# Schematic.net
KiCad netlist of a schematic drawn in EasyEDA Pro
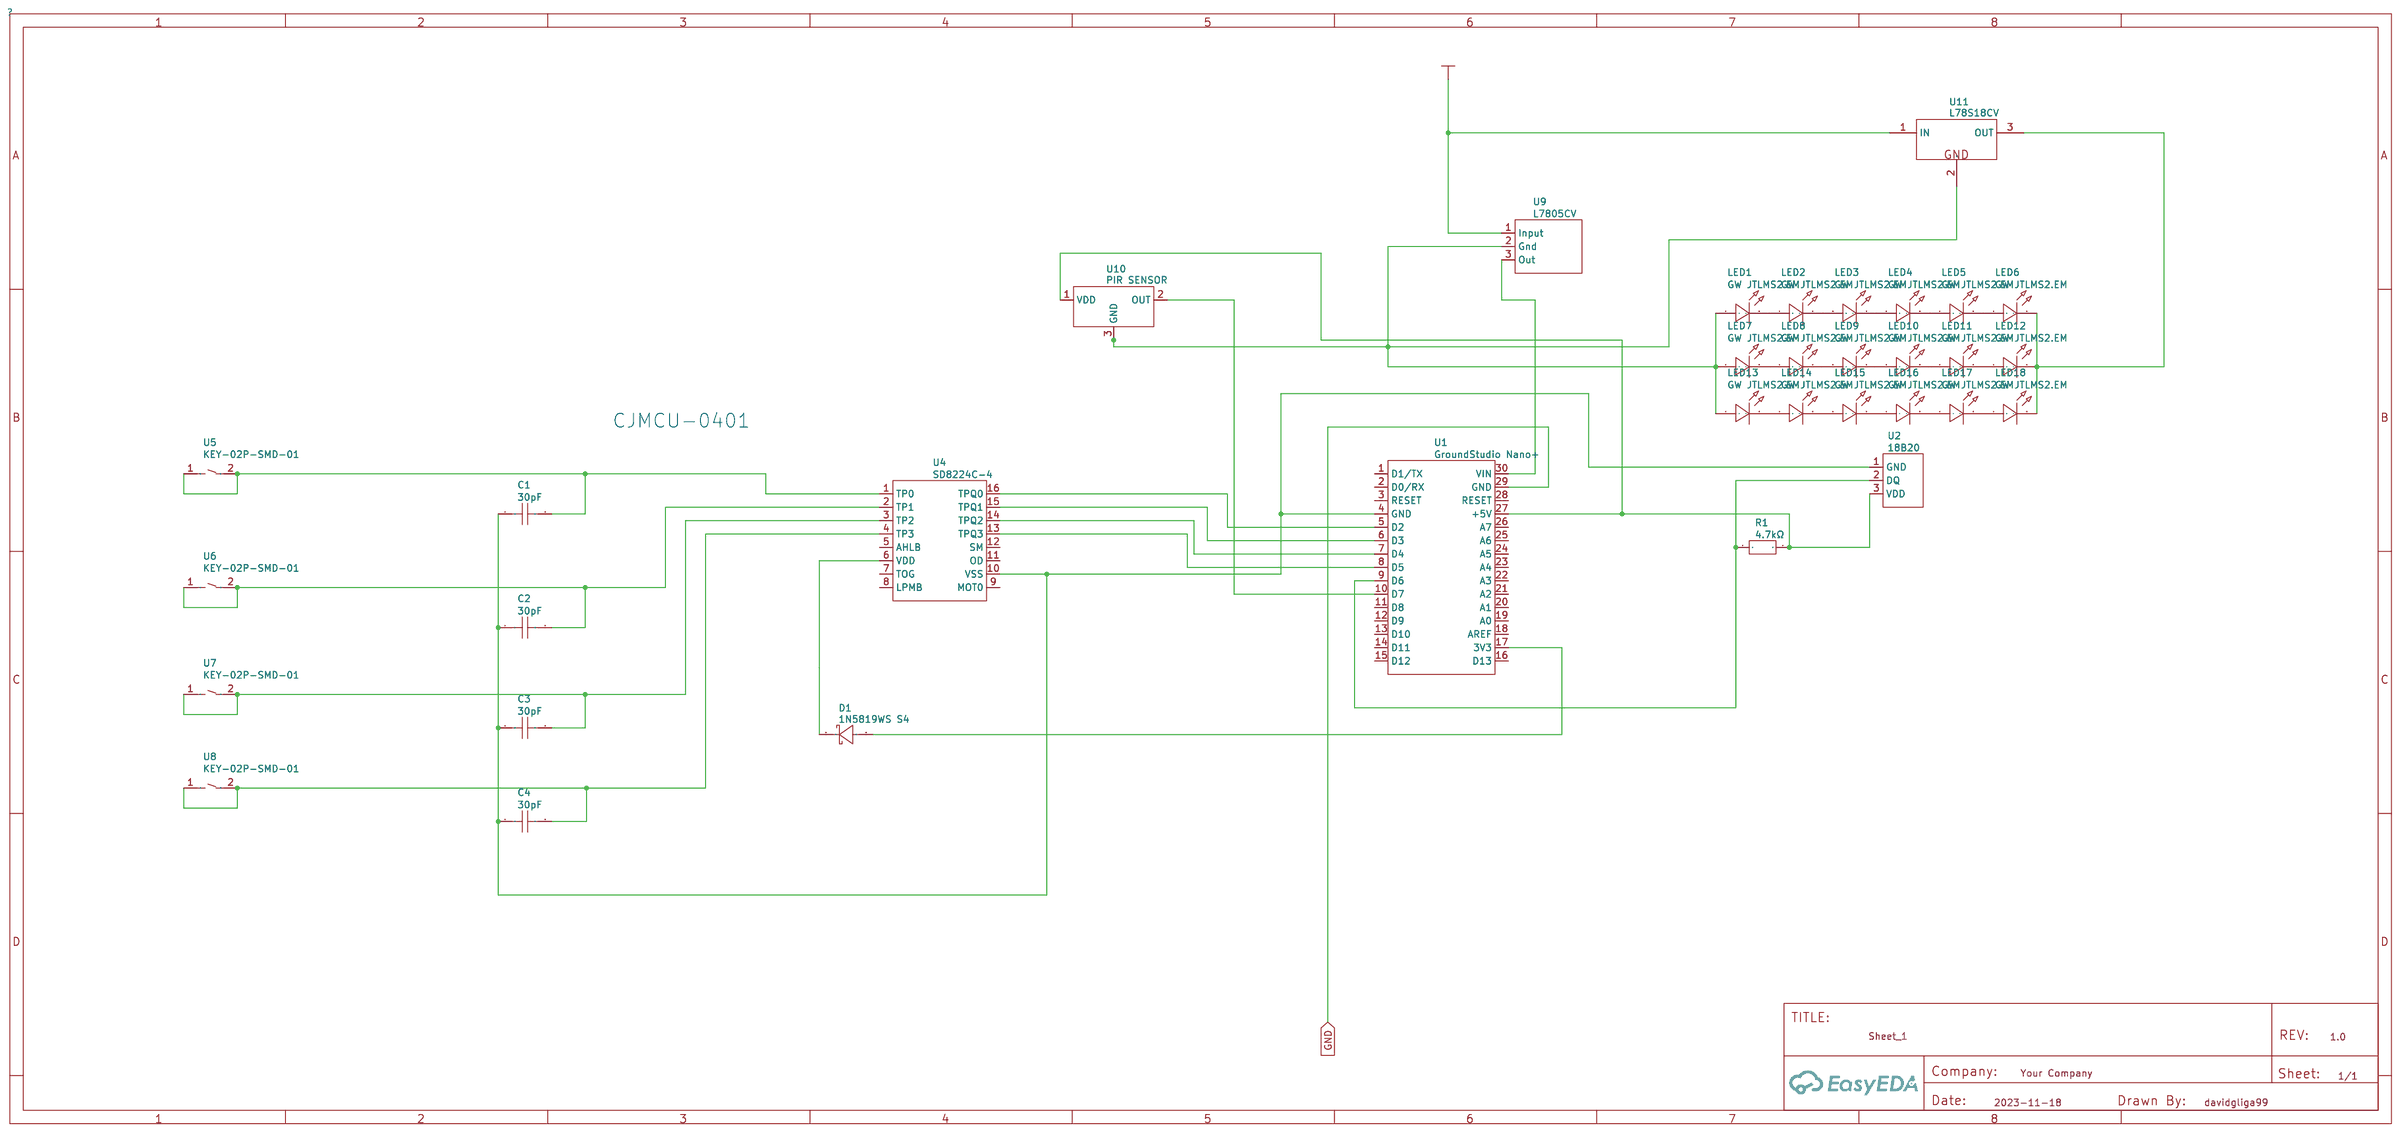
[diagram p0: schematic sheet]

(export (version "E")
  (design (tool "Eeschema 10.0.6"))
  (components
    (comp (ref "C1")
      (value "30pF")
      (footprint "easyedapro:C0402")
      (fields
        (field (name "Manufacturer Part") "AC0402JRNPO9BN300")
        (field (name "Manufacturer") "YAGEO(国巨)")
      )
      (libsource (lib "easyedapro") (part "30pF"))
    )
    (comp (ref "C2")
      (value "30pF")
      (footprint "easyedapro:C0402")
      (fields
        (field (name "Manufacturer Part") "AC0402JRNPO9BN300")
        (field (name "Manufacturer") "YAGEO(国巨)")
      )
      (libsource (lib "easyedapro") (part "30pF"))
    )
    (comp (ref "C3")
      (value "30pF")
      (footprint "easyedapro:C0402")
      (fields
        (field (name "Manufacturer Part") "AC0402JRNPO9BN300")
        (field (name "Manufacturer") "YAGEO(国巨)")
      )
      (libsource (lib "easyedapro") (part "30pF"))
    )
    (comp (ref "C4")
      (value "30pF")
      (footprint "easyedapro:C0402")
      (fields
        (field (name "Manufacturer Part") "AC0402JRNPO9BN300")
        (field (name "Manufacturer") "YAGEO(国巨)")
      )
      (libsource (lib "easyedapro") (part "30pF"))
    )
    (comp (ref "D1")
      (value "1N5819WS S4")
      (footprint "easyedapro:SOD-323_L1.6-W1.3-LS2.7-RD")
      (fields (field (name "Manufacturer") "JSMSEMI(杰盛微)"))
      (libsource (lib "easyedapro") (part "1N5819WS S4"))
    )
    (comp (ref "LED1")
      (value "GW JTLMS2.EM")
      (footprint "easyedapro:LED-SMD_L3.5-W2.8_28353V60MA6500K")
      (libsource (lib "easyedapro") (part "GW JTLMS2.EM"))
    )
    (comp (ref "LED2")
      (value "GW JTLMS2.EM")
      (footprint "easyedapro:LED-SMD_L3.5-W2.8_28353V60MA6500K")
      (libsource (lib "easyedapro") (part "GW JTLMS2.EM"))
    )
    (comp (ref "LED3")
      (value "GW JTLMS2.EM")
      (footprint "easyedapro:LED-SMD_L3.5-W2.8_28353V60MA6500K")
      (libsource (lib "easyedapro") (part "GW JTLMS2.EM"))
    )
    (comp (ref "LED4")
      (value "GW JTLMS2.EM")
      (footprint "easyedapro:LED-SMD_L3.5-W2.8_28353V60MA6500K")
      (libsource (lib "easyedapro") (part "GW JTLMS2.EM"))
    )
    (comp (ref "LED5")
      (value "GW JTLMS2.EM")
      (footprint "easyedapro:LED-SMD_L3.5-W2.8_28353V60MA6500K")
      (libsource (lib "easyedapro") (part "GW JTLMS2.EM"))
    )
    (comp (ref "LED6")
      (value "GW JTLMS2.EM")
      (footprint "easyedapro:LED-SMD_L3.5-W2.8_28353V60MA6500K")
      (libsource (lib "easyedapro") (part "GW JTLMS2.EM"))
    )
    (comp (ref "LED7")
      (value "GW JTLMS2.EM")
      (footprint "easyedapro:LED-SMD_L3.5-W2.8_28353V60MA6500K")
      (libsource (lib "easyedapro") (part "GW JTLMS2.EM"))
    )
    (comp (ref "LED8")
      (value "GW JTLMS2.EM")
      (footprint "easyedapro:LED-SMD_L3.5-W2.8_28353V60MA6500K")
      (libsource (lib "easyedapro") (part "GW JTLMS2.EM"))
    )
    (comp (ref "LED9")
      (value "GW JTLMS2.EM")
      (footprint "easyedapro:LED-SMD_L3.5-W2.8_28353V60MA6500K")
      (libsource (lib "easyedapro") (part "GW JTLMS2.EM"))
    )
    (comp (ref "LED10")
      (value "GW JTLMS2.EM")
      (footprint "easyedapro:LED-SMD_L3.5-W2.8_28353V60MA6500K")
      (libsource (lib "easyedapro") (part "GW JTLMS2.EM"))
    )
    (comp (ref "LED11")
      (value "GW JTLMS2.EM")
      (footprint "easyedapro:LED-SMD_L3.5-W2.8_28353V60MA6500K")
      (libsource (lib "easyedapro") (part "GW JTLMS2.EM"))
    )
    (comp (ref "LED12")
      (value "GW JTLMS2.EM")
      (footprint "easyedapro:LED-SMD_L3.5-W2.8_28353V60MA6500K")
      (libsource (lib "easyedapro") (part "GW JTLMS2.EM"))
    )
    (comp (ref "LED13")
      (value "GW JTLMS2.EM")
      (footprint "easyedapro:LED-SMD_L3.5-W2.8_28353V60MA6500K")
      (libsource (lib "easyedapro") (part "GW JTLMS2.EM"))
    )
    (comp (ref "LED14")
      (value "GW JTLMS2.EM")
      (footprint "easyedapro:LED-SMD_L3.5-W2.8_28353V60MA6500K")
      (libsource (lib "easyedapro") (part "GW JTLMS2.EM"))
    )
    (comp (ref "LED15")
      (value "GW JTLMS2.EM")
      (footprint "easyedapro:LED-SMD_L3.5-W2.8_28353V60MA6500K")
      (libsource (lib "easyedapro") (part "GW JTLMS2.EM"))
    )
    (comp (ref "LED16")
      (value "GW JTLMS2.EM")
      (footprint "easyedapro:LED-SMD_L3.5-W2.8_28353V60MA6500K")
      (libsource (lib "easyedapro") (part "GW JTLMS2.EM"))
    )
    (comp (ref "LED17")
      (value "GW JTLMS2.EM")
      (footprint "easyedapro:LED-SMD_L3.5-W2.8_28353V60MA6500K")
      (libsource (lib "easyedapro") (part "GW JTLMS2.EM"))
    )
    (comp (ref "LED18")
      (value "GW JTLMS2.EM")
      (footprint "easyedapro:LED-SMD_L3.5-W2.8_28353V60MA6500K")
      (libsource (lib "easyedapro") (part "GW JTLMS2.EM"))
    )
    (comp (ref "R1")
      (value "4.7kΩ")
      (footprint "easyedapro:RES-TH_BD2.4-L6.3-P10.30-D0.6")
      (fields
        (field (name "Manufacturer Part") "RN1/2WS4.7KΩFT/BA1")
        (field (name "Manufacturer") "Tyohm(幸亚电阻)")
      )
      (libsource (lib "easyedapro") (part "4.7kΩ"))
    )
    (comp (ref "U1")
      (value "GroundStudio Nano+")
      (footprint "easyedapro:COMM-TH_ARDUINO_NANO")
      (fields (field (name "Manufacturer Part") "ARDUINO_NANO"))
      (libsource (lib "easyedapro") (part "GroundStudio Nano+"))
    )
    (comp (ref "U2")
      (value "18B20")
      (footprint "easyedapro:TO-92-3_L4.9-W3.7-P2.54-L")
      (fields (field (name "Manufacturer") "I-CORE(中微爱芯)"))
      (libsource (lib "easyedapro") (part "18B20"))
    )
    (comp (ref "U4")
      (value "SD8224C-4")
      (footprint "easyedapro:SOP-16_L10.0-W3.9-P1.27-LS6.0-BL")
      (fields (field (name "Manufacturer") "SHOUDING(首鼎半导体)"))
      (libsource (lib "easyedapro") (part "SD8224C-4"))
    )
    (comp (ref "U5")
      (value "KEY-02P-SMD-01")
      (footprint "easyedapro:KEY-SMD_L4.0-W3.0-LS4.9")
      (libsource (lib "easyedapro") (part "KEY-02P-SMD-01"))
    )
    (comp (ref "U6")
      (value "KEY-02P-SMD-01")
      (footprint "easyedapro:KEY-SMD_L4.0-W3.0-LS4.9")
      (libsource (lib "easyedapro") (part "KEY-02P-SMD-01"))
    )
    (comp (ref "U7")
      (value "KEY-02P-SMD-01")
      (footprint "easyedapro:KEY-SMD_L4.0-W3.0-LS4.9")
      (libsource (lib "easyedapro") (part "KEY-02P-SMD-01"))
    )
    (comp (ref "U8")
      (value "KEY-02P-SMD-01")
      (footprint "easyedapro:KEY-SMD_L4.0-W3.0-LS4.9")
      (libsource (lib "easyedapro") (part "KEY-02P-SMD-01"))
    )
    (comp (ref "U9")
      (value "L7805CV")
      (footprint "easyedapro:TO-220-3_L10.0-W4.5-P2.54-L")
      (fields (field (name "Manufacturer") "UMW(广东友台半导体)"))
      (libsource (lib "easyedapro") (part "L7805CV"))
    )
    (comp (ref "U10")
      (value "PIR SENSOR")
      (footprint "easyedapro:PIR-TH_EKMB4308112K")
      (fields (field (name "Manufacturer Part") "EKMC1609112") (field (name "Manufacturer") "PANASONIC(松下)"))
      (libsource (lib "easyedapro") (part "PIR SENSOR"))
    )
    (comp (ref "U11") (value "L78S18CV") (libsource (lib "easyedapro") (part "L78S18CV")))
  )
  (nets
    (net (code "1") (name "24V") (class "Default")
      (node (ref "U11") (pin "1") (pinfunction "IN_1") (pintype "unspecified"))
      (node (ref "U9") (pin "1") (pinfunction "Input_1") (pintype "unspecified"))
    )
    (net (code "2") (name "GND") (class "Default")
      (node (ref "U1") (pin "29") (pinfunction "GND_29") (pintype "unspecified"))
    )
    (net (code "3") (name "Net-(D1-A)") (class "Default")
      (node (ref "D1") (pin "2") (pinfunction "A_2") (pintype "unspecified"))
      (node (ref "U1") (pin "17") (pinfunction "3V3_17") (pintype "unspecified"))
    )
    (net (code "4") (name "Net-(D1-C)") (class "Default")
      (node (ref "D1") (pin "1") (pinfunction "C_1") (pintype "unspecified"))
      (node (ref "U4") (pin "6") (pinfunction "VDD_6") (pintype "unspecified"))
    )
    (net (code "5") (name "Net-(LED1-+)") (class "Default")
      (node (ref "LED1") (pin "1") (pinfunction "+_1") (pintype "unspecified"))
      (node (ref "LED13") (pin "1") (pinfunction "+_1") (pintype "unspecified"))
      (node (ref "LED7") (pin "1") (pinfunction "+_1") (pintype "unspecified"))
      (node (ref "U10") (pin "3") (pinfunction "GND_3") (pintype "unspecified"))
      (node (ref "U11") (pin "2") (pinfunction "GND_2") (pintype "unspecified"))
      (node (ref "U9") (pin "2") (pinfunction "Gnd_2") (pintype "unspecified"))
    )
    (net (code "6") (name "Net-(LED1--)") (class "Default")
      (node (ref "LED1") (pin "2") (pinfunction "-_2") (pintype "unspecified"))
      (node (ref "LED2") (pin "1") (pinfunction "+_1") (pintype "unspecified"))
    )
    (net (code "7") (name "Net-(LED2--)") (class "Default")
      (node (ref "LED2") (pin "2") (pinfunction "-_2") (pintype "unspecified"))
      (node (ref "LED3") (pin "1") (pinfunction "+_1") (pintype "unspecified"))
    )
    (net (code "8") (name "Net-(LED3--)") (class "Default")
      (node (ref "LED3") (pin "2") (pinfunction "-_2") (pintype "unspecified"))
      (node (ref "LED4") (pin "1") (pinfunction "+_1") (pintype "unspecified"))
    )
    (net (code "9") (name "Net-(LED4--)") (class "Default")
      (node (ref "LED4") (pin "2") (pinfunction "-_2") (pintype "unspecified"))
      (node (ref "LED5") (pin "1") (pinfunction "+_1") (pintype "unspecified"))
    )
    (net (code "10") (name "Net-(LED5--)") (class "Default")
      (node (ref "LED5") (pin "2") (pinfunction "-_2") (pintype "unspecified"))
      (node (ref "LED6") (pin "1") (pinfunction "+_1") (pintype "unspecified"))
    )
    (net (code "11") (name "Net-(LED7--)") (class "Default")
      (node (ref "LED7") (pin "2") (pinfunction "-_2") (pintype "unspecified"))
      (node (ref "LED8") (pin "1") (pinfunction "+_1") (pintype "unspecified"))
    )
    (net (code "12") (name "Net-(LED8--)") (class "Default")
      (node (ref "LED8") (pin "2") (pinfunction "-_2") (pintype "unspecified"))
      (node (ref "LED9") (pin "1") (pinfunction "+_1") (pintype "unspecified"))
    )
    (net (code "13") (name "Net-(LED10-+)") (class "Default")
      (node (ref "LED10") (pin "1") (pinfunction "+_1") (pintype "unspecified"))
      (node (ref "LED9") (pin "2") (pinfunction "-_2") (pintype "unspecified"))
    )
    (net (code "14") (name "Net-(LED10--)") (class "Default")
      (node (ref "LED10") (pin "2") (pinfunction "-_2") (pintype "unspecified"))
      (node (ref "LED11") (pin "1") (pinfunction "+_1") (pintype "unspecified"))
    )
    (net (code "15") (name "Net-(LED11--)") (class "Default")
      (node (ref "LED11") (pin "2") (pinfunction "-_2") (pintype "unspecified"))
      (node (ref "LED12") (pin "1") (pinfunction "+_1") (pintype "unspecified"))
    )
    (net (code "16") (name "Net-(LED12--)") (class "Default")
      (node (ref "LED12") (pin "2") (pinfunction "-_2") (pintype "unspecified"))
      (node (ref "LED18") (pin "2") (pinfunction "-_2") (pintype "unspecified"))
      (node (ref "LED6") (pin "2") (pinfunction "-_2") (pintype "unspecified"))
      (node (ref "U11") (pin "3") (pinfunction "OUT_3") (pintype "unspecified"))
    )
    (net (code "17") (name "Net-(LED13--)") (class "Default")
      (node (ref "LED13") (pin "2") (pinfunction "-_2") (pintype "unspecified"))
      (node (ref "LED14") (pin "1") (pinfunction "+_1") (pintype "unspecified"))
    )
    (net (code "18") (name "Net-(LED14--)") (class "Default")
      (node (ref "LED14") (pin "2") (pinfunction "-_2") (pintype "unspecified"))
      (node (ref "LED15") (pin "1") (pinfunction "+_1") (pintype "unspecified"))
    )
    (net (code "19") (name "Net-(LED15--)") (class "Default")
      (node (ref "LED15") (pin "2") (pinfunction "-_2") (pintype "unspecified"))
      (node (ref "LED16") (pin "1") (pinfunction "+_1") (pintype "unspecified"))
    )
    (net (code "20") (name "Net-(LED16--)") (class "Default")
      (node (ref "LED16") (pin "2") (pinfunction "-_2") (pintype "unspecified"))
      (node (ref "LED17") (pin "1") (pinfunction "+_1") (pintype "unspecified"))
    )
    (net (code "21") (name "Net-(LED17--)") (class "Default")
      (node (ref "LED17") (pin "2") (pinfunction "-_2") (pintype "unspecified"))
      (node (ref "LED18") (pin "1") (pinfunction "+_1") (pintype "unspecified"))
    )
    (net (code "22") (name "Net-(U1-+5V)") (class "Default")
      (node (ref "R1") (pin "2") (pinfunction "2_2") (pintype "unspecified"))
      (node (ref "U1") (pin "27") (pinfunction "+5V_27") (pintype "unspecified"))
      (node (ref "U10") (pin "1") (pinfunction "VDD_1") (pintype "unspecified"))
      (node (ref "U2") (pin "3") (pinfunction "VDD_3") (pintype "unspecified"))
    )
    (net (code "23") (name "Net-(U1-D2)") (class "Default")
      (node (ref "U1") (pin "5") (pinfunction "D2_5") (pintype "unspecified"))
      (node (ref "U4") (pin "16") (pinfunction "TPQ0_16") (pintype "unspecified"))
    )
    (net (code "24") (name "Net-(U1-D3)") (class "Default")
      (node (ref "U1") (pin "6") (pinfunction "D3_6") (pintype "unspecified"))
      (node (ref "U4") (pin "15") (pinfunction "TPQ1_15") (pintype "unspecified"))
    )
    (net (code "25") (name "Net-(U1-D4)") (class "Default")
      (node (ref "U1") (pin "7") (pinfunction "D4_7") (pintype "unspecified"))
      (node (ref "U4") (pin "14") (pinfunction "TPQ2_14") (pintype "unspecified"))
    )
    (net (code "26") (name "Net-(U1-D5)") (class "Default")
      (node (ref "U1") (pin "8") (pinfunction "D5_8") (pintype "unspecified"))
      (node (ref "U4") (pin "13") (pinfunction "TPQ3_13") (pintype "unspecified"))
    )
    (net (code "27") (name "Net-(U1-D6)") (class "Default")
      (node (ref "R1") (pin "1") (pinfunction "1_1") (pintype "unspecified"))
      (node (ref "U1") (pin "9") (pinfunction "D6_9") (pintype "unspecified"))
      (node (ref "U2") (pin "2") (pinfunction "DQ_2") (pintype "unspecified"))
    )
    (net (code "28") (name "Net-(U1-D7)") (class "Default")
      (node (ref "U1") (pin "10") (pinfunction "D7_10") (pintype "unspecified"))
      (node (ref "U10") (pin "2") (pinfunction "OUT_2") (pintype "unspecified"))
    )
    (net (code "29") (name "Net-(U1-VIN)") (class "Default")
      (node (ref "U1") (pin "30") (pinfunction "VIN_30") (pintype "unspecified"))
      (node (ref "U9") (pin "3") (pinfunction "Out_3") (pintype "unspecified"))
    )
    (net (code "30") (name "Net-(U2-GND)") (class "Default")
      (node (ref "C1") (pin "1") (pinfunction "1_1") (pintype "unspecified"))
      (node (ref "C2") (pin "1") (pinfunction "1_1") (pintype "unspecified"))
      (node (ref "C3") (pin "1") (pinfunction "1_1") (pintype "unspecified"))
      (node (ref "C4") (pin "1") (pinfunction "1_1") (pintype "unspecified"))
      (node (ref "U1") (pin "4") (pinfunction "GND_4") (pintype "unspecified"))
      (node (ref "U2") (pin "1") (pinfunction "GND_1") (pintype "unspecified"))
      (node (ref "U4") (pin "10") (pinfunction "VSS_10") (pintype "unspecified"))
    )
    (net (code "31") (name "Net-(U4-TP0)") (class "Default")
      (node (ref "C1") (pin "2") (pinfunction "2_2") (pintype "unspecified"))
      (node (ref "U4") (pin "1") (pinfunction "TP0_1") (pintype "unspecified"))
      (node (ref "U5") (pin "1") (pinfunction "1_1") (pintype "unspecified"))
      (node (ref "U5") (pin "2") (pinfunction "2_2") (pintype "unspecified"))
    )
    (net (code "32") (name "Net-(U4-TP1)") (class "Default")
      (node (ref "C2") (pin "2") (pinfunction "2_2") (pintype "unspecified"))
      (node (ref "U4") (pin "2") (pinfunction "TP1_2") (pintype "unspecified"))
      (node (ref "U6") (pin "1") (pinfunction "1_1") (pintype "unspecified"))
      (node (ref "U6") (pin "2") (pinfunction "2_2") (pintype "unspecified"))
    )
    (net (code "33") (name "Net-(U4-TP2)") (class "Default")
      (node (ref "C3") (pin "2") (pinfunction "2_2") (pintype "unspecified"))
      (node (ref "U4") (pin "3") (pinfunction "TP2_3") (pintype "unspecified"))
      (node (ref "U7") (pin "1") (pinfunction "1_1") (pintype "unspecified"))
      (node (ref "U7") (pin "2") (pinfunction "2_2") (pintype "unspecified"))
    )
    (net (code "34") (name "Net-(U4-TP3)") (class "Default")
      (node (ref "C4") (pin "2") (pinfunction "2_2") (pintype "unspecified"))
      (node (ref "U4") (pin "4") (pinfunction "TP3_4") (pintype "unspecified"))
      (node (ref "U8") (pin "1") (pinfunction "1_1") (pintype "unspecified"))
      (node (ref "U8") (pin "2") (pinfunction "2_2") (pintype "unspecified"))
    )
    (net (code "35") (name "unconnected-(U1-A0-Pad19)") (class "Default")
      (node (ref "U1") (pin "19") (pinfunction "A0_19") (pintype "unspecified"))
    )
    (net (code "36") (name "unconnected-(U1-A1-Pad20)") (class "Default")
      (node (ref "U1") (pin "20") (pinfunction "A1_20") (pintype "unspecified"))
    )
    (net (code "37") (name "unconnected-(U1-A2-Pad21)") (class "Default")
      (node (ref "U1") (pin "21") (pinfunction "A2_21") (pintype "unspecified"))
    )
    (net (code "38") (name "unconnected-(U1-A3-Pad22)") (class "Default")
      (node (ref "U1") (pin "22") (pinfunction "A3_22") (pintype "unspecified"))
    )
    (net (code "39") (name "unconnected-(U1-A4-Pad23)") (class "Default")
      (node (ref "U1") (pin "23") (pinfunction "A4_23") (pintype "unspecified"))
    )
    (net (code "40") (name "unconnected-(U1-A5-Pad24)") (class "Default")
      (node (ref "U1") (pin "24") (pinfunction "A5_24") (pintype "unspecified"))
    )
    (net (code "41") (name "unconnected-(U1-A6-Pad25)") (class "Default")
      (node (ref "U1") (pin "25") (pinfunction "A6_25") (pintype "unspecified"))
    )
    (net (code "42") (name "unconnected-(U1-A7-Pad26)") (class "Default")
      (node (ref "U1") (pin "26") (pinfunction "A7_26") (pintype "unspecified"))
    )
    (net (code "43") (name "unconnected-(U1-AREF-Pad18)") (class "Default")
      (node (ref "U1") (pin "18") (pinfunction "AREF_18") (pintype "unspecified"))
    )
    (net (code "44") (name "unconnected-(U1-D0{slash}RX-Pad2)") (class "Default")
      (node (ref "U1") (pin "2") (pinfunction "D0/RX_2") (pintype "unspecified"))
    )
    (net (code "45") (name "unconnected-(U1-D1{slash}TX-Pad1)") (class "Default")
      (node (ref "U1") (pin "1") (pinfunction "D1/TX_1") (pintype "unspecified"))
    )
    (net (code "46") (name "unconnected-(U1-D8-Pad11)") (class "Default")
      (node (ref "U1") (pin "11") (pinfunction "D8_11") (pintype "unspecified"))
    )
    (net (code "47") (name "unconnected-(U1-D9-Pad12)") (class "Default")
      (node (ref "U1") (pin "12") (pinfunction "D9_12") (pintype "unspecified"))
    )
    (net (code "48") (name "unconnected-(U1-D10-Pad13)") (class "Default")
      (node (ref "U1") (pin "13") (pinfunction "D10_13") (pintype "unspecified"))
    )
    (net (code "49") (name "unconnected-(U1-D11-Pad14)") (class "Default")
      (node (ref "U1") (pin "14") (pinfunction "D11_14") (pintype "unspecified"))
    )
    (net (code "50") (name "unconnected-(U1-D12-Pad15)") (class "Default")
      (node (ref "U1") (pin "15") (pinfunction "D12_15") (pintype "unspecified"))
    )
    (net (code "51") (name "unconnected-(U1-D13-Pad16)") (class "Default")
      (node (ref "U1") (pin "16") (pinfunction "D13_16") (pintype "unspecified"))
    )
    (net (code "52") (name "unconnected-(U1-RESET-Pad3)") (class "Default")
      (node (ref "U1") (pin "3") (pinfunction "RESET_3") (pintype "unspecified"))
    )
    (net (code "53") (name "unconnected-(U1-RESET-Pad28)") (class "Default")
      (node (ref "U1") (pin "28") (pinfunction "RESET_28") (pintype "unspecified"))
    )
    (net (code "54") (name "unconnected-(U4-AHLB-Pad5)") (class "Default")
      (node (ref "U4") (pin "5") (pinfunction "AHLB_5") (pintype "unspecified"))
    )
    (net (code "55") (name "unconnected-(U4-LPMB-Pad8)") (class "Default")
      (node (ref "U4") (pin "8") (pinfunction "LPMB_8") (pintype "unspecified"))
    )
    (net (code "56") (name "unconnected-(U4-MOT0-Pad9)") (class "Default")
      (node (ref "U4") (pin "9") (pinfunction "MOT0_9") (pintype "unspecified"))
    )
    (net (code "57") (name "unconnected-(U4-OD-Pad11)") (class "Default")
      (node (ref "U4") (pin "11") (pinfunction "OD_11") (pintype "unspecified"))
    )
    (net (code "58") (name "unconnected-(U4-SM-Pad12)") (class "Default")
      (node (ref "U4") (pin "12") (pinfunction "SM_12") (pintype "unspecified"))
    )
    (net (code "59") (name "unconnected-(U4-TOG-Pad7)") (class "Default")
      (node (ref "U4") (pin "7") (pinfunction "TOG_7") (pintype "unspecified"))
    )
  )
)
